# sbc.net
KiCad netlist of a schematic drawn in Altium Designer
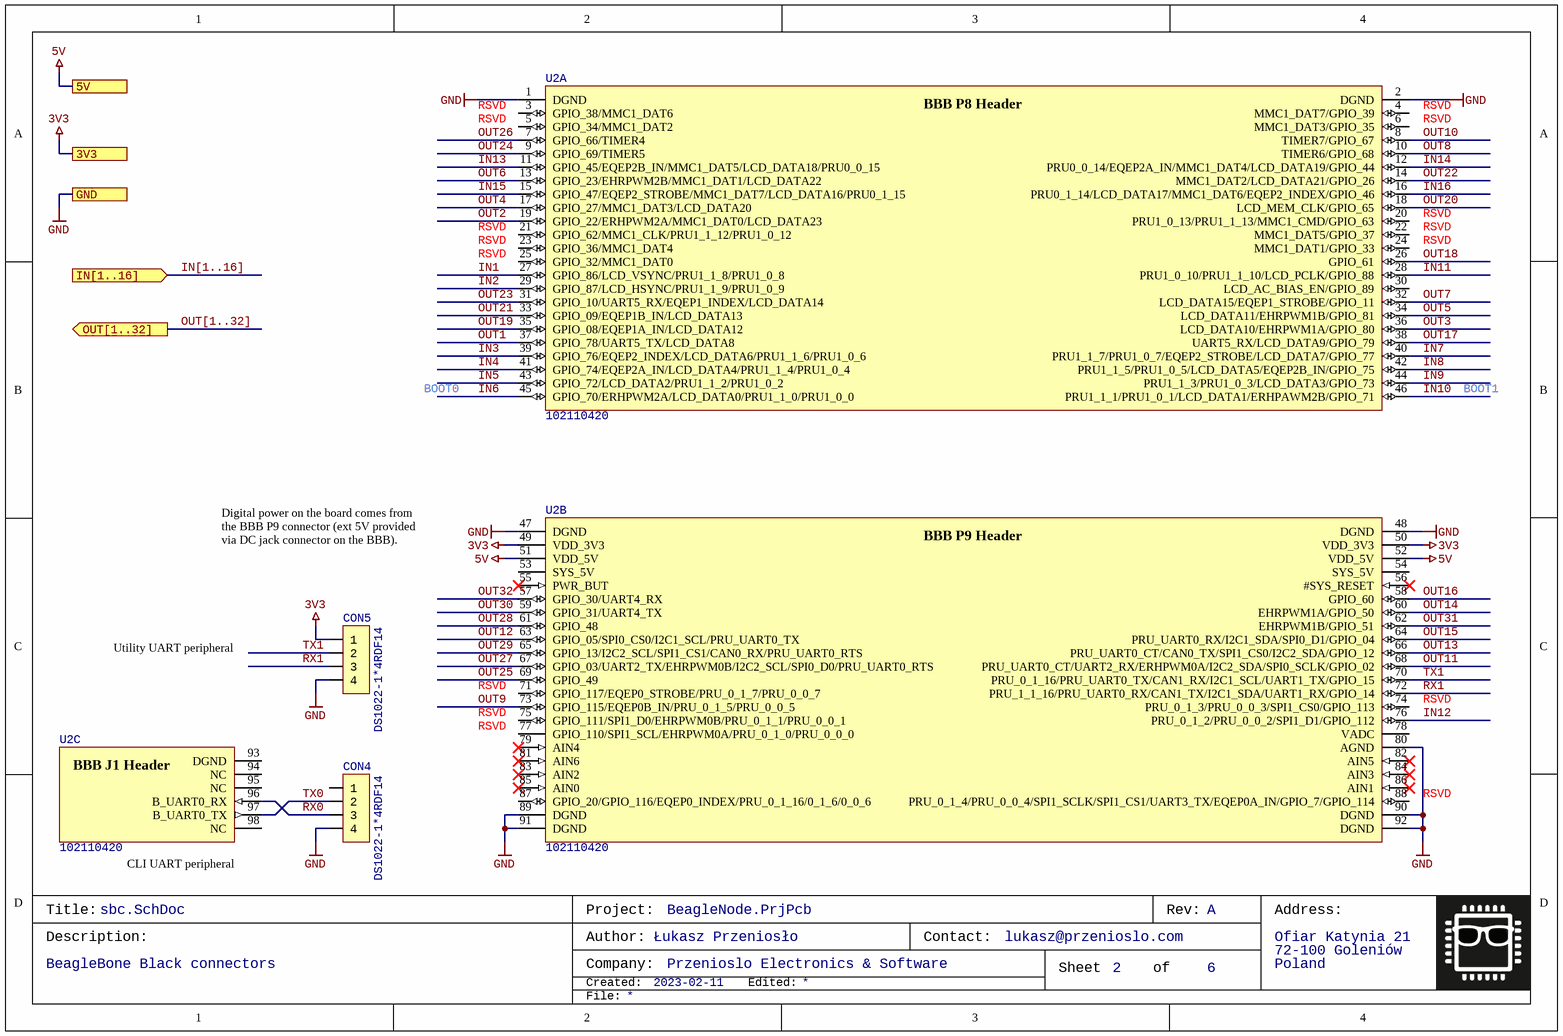
[diagram p0: sbc.SchDoc]

(export (version "E")
  (design (tool "Eeschema 10.0.6"))
  (components
    (comp (ref "CON4")
      (value "DS1022-1*4RDF14")
      (footprint "HMTA_1X4_2.54_3.60")
      (description "Pin header; pin strips; C-Grid III; male; PIN: 4; angled 90°; THT")
      (fields (field (name "MANUFACTURER") "CONNFLY"))
      (libsource (lib "connector") (part "HMTA_1X4_2.54_3.60"))
    )
    (comp (ref "CON5")
      (value "DS1022-1*4RDF14")
      (footprint "HMTA_1X4_2.54_3.60")
      (description "Pin header; pin strips; C-Grid III; male; PIN: 4; angled 90°; THT")
      (fields (field (name "MANUFACTURER") "CONNFLY"))
      (libsource (lib "connector") (part "HMTA_1X4_2.54_3.60"))
    )
    (comp (ref "U2")
      (value "102110420")
      (footprint "BeagleBone Black No Bat")
      (description "BeagleBone Black female headers without the battery 4 pin header")
      (fields (field (name "MANUFACTURER") "BeagleBoard"))
      (libsource (lib "shield") (part "Beaglebone Black No Bat"))
    )
  )
  (nets
    (net (code "1") (name "/IN1") (class "Default")
      (node (ref "U2") (pin "27") (pinfunction "GPIO_86/LCD_VSYNC/PRU1_1_8/PRU1_0_8_27") (pintype "bidirectional"))
    )
    (net (code "2") (name "/IN2") (class "Default")
      (node (ref "U2") (pin "29") (pinfunction "GPIO_87/LCD_HSYNC/PRU1_1_9/PRU1_0_9_29") (pintype "bidirectional"))
    )
    (net (code "3") (name "/IN3") (class "Default")
      (node (ref "U2") (pin "39") (pinfunction "GPIO_76/EQEP2_INDEX/LCD_DATA6/PRU1_1_6/PRU1_0_6_39") (pintype "bidirectional"))
    )
    (net (code "4") (name "/IN4") (class "Default")
      (node (ref "U2") (pin "41") (pinfunction "GPIO_74/EQEP2A_IN/LCD_DATA4/PRU1_1_4/PRU1_0_4_41") (pintype "bidirectional"))
    )
    (net (code "5") (name "/IN5") (class "Default")
      (node (ref "U2") (pin "43") (pinfunction "GPIO_72/LCD_DATA2/PRU1_1_2/PRU1_0_2_43") (pintype "bidirectional"))
    )
    (net (code "6") (name "/IN6") (class "Default")
      (node (ref "U2") (pin "45") (pinfunction "GPIO_70/ERHPWM2A/LCD_DATA0/PRU1_1_0/PRU1_0_0_45") (pintype "bidirectional"))
    )
    (net (code "7") (name "/IN7") (class "Default")
      (node (ref "U2") (pin "40") (pinfunction "PRU1_1_7/PRU1_0_7/EQEP2_STROBE/LCD_DATA7/GPIO_77_40") (pintype "bidirectional"))
    )
    (net (code "8") (name "/IN8") (class "Default")
      (node (ref "U2") (pin "42") (pinfunction "PRU1_1_5/PRU1_0_5/LCD_DATA5/EQEP2B_IN/GPIO_75_42") (pintype "bidirectional"))
    )
    (net (code "9") (name "/IN9") (class "Default")
      (node (ref "U2") (pin "44") (pinfunction "PRU1_1_3/PRU1_0_3/LCD_DATA3/GPIO_73_44") (pintype "bidirectional"))
    )
    (net (code "10") (name "/IN10") (class "Default")
      (node (ref "U2") (pin "46") (pinfunction "PRU1_1_1/PRU1_0_1/LCD_DATA1/ERHPAWM2B/GPIO_71_46") (pintype "bidirectional"))
    )
    (net (code "11") (name "/IN11") (class "Default")
      (node (ref "U2") (pin "28") (pinfunction "PRU1_0_10/PRU1_1_10/LCD_PCLK/GPIO_88_28") (pintype "bidirectional"))
    )
    (net (code "12") (name "/IN12") (class "Default")
      (node (ref "U2") (pin "76") (pinfunction "PRU_0_1_2/PRU_0_0_2/SPI1_D1/GPIO_112_76") (pintype "bidirectional"))
    )
    (net (code "13") (name "/IN13") (class "Default")
      (node (ref "U2") (pin "11") (pinfunction "GPIO_45/EQEP2B_IN/MMC1_DAT5/LCD_DATA18/PRU0_0_15_11") (pintype "bidirectional"))
    )
    (net (code "14") (name "/IN14") (class "Default")
      (node (ref "U2") (pin "12") (pinfunction "PRU0_0_14/EQEP2A_IN/MMC1_DAT4/LCD_DATA19/GPIO_44_12") (pintype "bidirectional"))
    )
    (net (code "15") (name "/IN15") (class "Default")
      (node (ref "U2") (pin "15") (pinfunction "GPIO_47/EQEP2_STROBE/MMC1_DAT7/LCD_DATA16/PRU0_1_15_15") (pintype "bidirectional"))
    )
    (net (code "16") (name "/IN16") (class "Default")
      (node (ref "U2") (pin "16") (pinfunction "PRU0_1_14/LCD_DATA17/MMC1_DAT6/EQEP2_INDEX/GPIO_46_16") (pintype "bidirectional"))
    )
    (net (code "18") (name "/OUT1") (class "Default")
      (node (ref "U2") (pin "37") (pinfunction "GPIO_78/UART5_TX/LCD_DATA8_37") (pintype "bidirectional"))
    )
    (net (code "19") (name "/OUT2") (class "Default")
      (node (ref "U2") (pin "19") (pinfunction "GPIO_22/ERHPWM2A/MMC1_DAT0/LCD_DATA23_19") (pintype "bidirectional"))
    )
    (net (code "20") (name "/OUT3") (class "Default")
      (node (ref "U2") (pin "36") (pinfunction "LCD_DATA10/EHRPWM1A/GPIO_80_36") (pintype "bidirectional"))
    )
    (net (code "21") (name "/OUT4") (class "Default")
      (node (ref "U2") (pin "17") (pinfunction "GPIO_27/MMC1_DAT3/LCD_DATA20_17") (pintype "bidirectional"))
    )
    (net (code "22") (name "/OUT5") (class "Default")
      (node (ref "U2") (pin "34") (pinfunction "LCD_DATA11/EHRPWM1B/GPIO_81_34") (pintype "bidirectional"))
    )
    (net (code "23") (name "/OUT6") (class "Default")
      (node (ref "U2") (pin "13") (pinfunction "GPIO_23/EHRPWM2B/MMC1_DAT1/LCD_DATA22_13") (pintype "bidirectional"))
    )
    (net (code "24") (name "/OUT7") (class "Default")
      (node (ref "U2") (pin "32") (pinfunction "LCD_DATA15/EQEP1_STROBE/GPIO_11_32") (pintype "bidirectional"))
    )
    (net (code "25") (name "/OUT8") (class "Default")
      (node (ref "U2") (pin "10") (pinfunction "TIMER6/GPIO_68_10") (pintype "bidirectional"))
    )
    (net (code "26") (name "/OUT9") (class "Default")
      (node (ref "U2") (pin "73") (pinfunction "GPIO_115/EQEP0B_IN/PRU_0_1_5/PRU_0_0_5_73") (pintype "bidirectional"))
    )
    (net (code "27") (name "/OUT10") (class "Default")
      (node (ref "U2") (pin "8") (pinfunction "TIMER7/GPIO_67_8") (pintype "bidirectional"))
    )
    (net (code "28") (name "/OUT11") (class "Default")
      (node (ref "U2") (pin "68") (pinfunction "PRU_UART0_CT/UART2_RX/ERHPWM0A/I2C2_SDA/SPI0_SCLK/GPIO_02_68") (pintype "bidirectional"))
    )
    (net (code "29") (name "/OUT12") (class "Default")
      (node (ref "U2") (pin "63") (pinfunction "GPIO_05/SPI0_CS0/I2C1_SCL/PRU_UART0_TX_63") (pintype "bidirectional"))
    )
    (net (code "30") (name "/OUT13") (class "Default")
      (node (ref "U2") (pin "66") (pinfunction "PRU_UART0_CT/CAN0_TX/SPI1_CS0/I2C2_SDA/GPIO_12_66") (pintype "bidirectional"))
    )
    (net (code "31") (name "/OUT14") (class "Default")
      (node (ref "U2") (pin "60") (pinfunction "EHRPWM1A/GPIO_50_60") (pintype "bidirectional"))
    )
    (net (code "32") (name "/OUT15") (class "Default")
      (node (ref "U2") (pin "64") (pinfunction "PRU_UART0_RX/I2C1_SDA/SPI0_D1/GPIO_04_64") (pintype "bidirectional"))
    )
    (net (code "33") (name "/OUT16") (class "Default")
      (node (ref "U2") (pin "58") (pinfunction "GPIO_60_58") (pintype "bidirectional"))
    )
    (net (code "34") (name "/OUT17") (class "Default")
      (node (ref "U2") (pin "38") (pinfunction "UART5_RX/LCD_DATA9/GPIO_79_38") (pintype "bidirectional"))
    )
    (net (code "35") (name "/OUT18") (class "Default")
      (node (ref "U2") (pin "26") (pinfunction "GPIO_61_26") (pintype "bidirectional"))
    )
    (net (code "36") (name "/OUT19") (class "Default")
      (node (ref "U2") (pin "35") (pinfunction "GPIO_08/EQEP1A_IN/LCD_DATA12_35") (pintype "bidirectional"))
    )
    (net (code "37") (name "/OUT20") (class "Default")
      (node (ref "U2") (pin "18") (pinfunction "LCD_MEM_CLK/GPIO_65_18") (pintype "bidirectional"))
    )
    (net (code "38") (name "/OUT21") (class "Default")
      (node (ref "U2") (pin "33") (pinfunction "GPIO_09/EQEP1B_IN/LCD_DATA13_33") (pintype "bidirectional"))
    )
    (net (code "39") (name "/OUT22") (class "Default")
      (node (ref "U2") (pin "14") (pinfunction "MMC1_DAT2/LCD_DATA21/GPIO_26_14") (pintype "bidirectional"))
    )
    (net (code "40") (name "/OUT23") (class "Default")
      (node (ref "U2") (pin "31") (pinfunction "GPIO_10/UART5_RX/EQEP1_INDEX/LCD_DATA14_31") (pintype "bidirectional"))
    )
    (net (code "41") (name "/OUT24") (class "Default")
      (node (ref "U2") (pin "9") (pinfunction "GPIO_69/TIMER5_9") (pintype "bidirectional"))
    )
    (net (code "42") (name "/OUT25") (class "Default")
      (node (ref "U2") (pin "69") (pinfunction "GPIO_49_69") (pintype "bidirectional"))
    )
    (net (code "43") (name "/OUT26") (class "Default")
      (node (ref "U2") (pin "7") (pinfunction "GPIO_66/TIMER4_7") (pintype "bidirectional"))
    )
    (net (code "44") (name "/OUT27") (class "Default")
      (node (ref "U2") (pin "67") (pinfunction "GPIO_03/UART2_TX/EHRPWM0B/I2C2_SCL/SPI0_D0/PRU_UART0_RTS_67") (pintype "bidirectional"))
    )
    (net (code "45") (name "/OUT28") (class "Default")
      (node (ref "U2") (pin "61") (pinfunction "GPIO_48_61") (pintype "bidirectional"))
    )
    (net (code "46") (name "/OUT29") (class "Default")
      (node (ref "U2") (pin "65") (pinfunction "GPIO_13/I2C2_SCL/SPI1_CS1/CAN0_RX/PRU_UART0_RTS_65") (pintype "bidirectional"))
    )
    (net (code "47") (name "/OUT30") (class "Default")
      (node (ref "U2") (pin "59") (pinfunction "GPIO_31/UART4_TX_59") (pintype "bidirectional"))
    )
    (net (code "48") (name "/OUT31") (class "Default")
      (node (ref "U2") (pin "62") (pinfunction "EHRPWM1B/GPIO_51_62") (pintype "bidirectional"))
    )
    (net (code "49") (name "/OUT32") (class "Default")
      (node (ref "U2") (pin "57") (pinfunction "GPIO_30/UART4_RX_57") (pintype "bidirectional"))
    )
    (net (code "51") (name "/RX0") (class "Default")
      (node (ref "CON4") (pin "3") (pinfunction "3_3") (pintype "passive"))
      (node (ref "U2") (pin "96") (pinfunction "B_UART0_RX_96") (pintype "input"))
    )
    (net (code "52") (name "/RX1") (class "Default")
      (node (ref "CON5") (pin "3") (pinfunction "3_3") (pintype "passive"))
      (node (ref "U2") (pin "72") (pinfunction "PRU_1_1_16/PRU_UART0_RX/CAN1_TX/I2C1_SDA/UART1_RX/GPIO_14_72") (pintype "bidirectional"))
    )
    (net (code "53") (name "/TX0") (class "Default")
      (node (ref "CON4") (pin "2") (pinfunction "2_2") (pintype "passive"))
      (node (ref "U2") (pin "97") (pinfunction "B_UART0_TX_97") (pintype "output"))
    )
    (net (code "54") (name "/TX1") (class "Default")
      (node (ref "CON5") (pin "2") (pinfunction "2_2") (pintype "passive"))
      (node (ref "U2") (pin "70") (pinfunction "PRU_0_1_16/PRU_UART0_TX/CAN1_RX/I2C1_SCL/UART1_TX/GPIO_15_70") (pintype "bidirectional"))
    )
    (net (code "55") (name "3V3") (class "Default")
      (node (ref "CON5") (pin "1") (pinfunction "1_1") (pintype "passive"))
      (node (ref "U2") (pin "49") (pinfunction "VDD_3V3_49") (pintype "power_in"))
      (node (ref "U2") (pin "50") (pinfunction "VDD_3V3_50") (pintype "power_in"))
    )
    (net (code "56") (name "5V") (class "Default")
      (node (ref "U2") (pin "51") (pinfunction "VDD_5V_51") (pintype "power_in"))
      (node (ref "U2") (pin "52") (pinfunction "VDD_5V_52") (pintype "power_in"))
    )
    (net (code "57") (name "GND") (class "Default")
      (node (ref "CON4") (pin "4") (pinfunction "4_4") (pintype "passive"))
      (node (ref "CON5") (pin "4") (pinfunction "4_4") (pintype "passive"))
      (node (ref "U2") (pin "1") (pinfunction "DGND_1") (pintype "power_in"))
      (node (ref "U2") (pin "2") (pinfunction "DGND_2") (pintype "power_in"))
      (node (ref "U2") (pin "47") (pinfunction "DGND_47") (pintype "power_in"))
      (node (ref "U2") (pin "48") (pinfunction "DGND_48") (pintype "power_in"))
      (node (ref "U2") (pin "80") (pinfunction "AGND_80") (pintype "power_in"))
      (node (ref "U2") (pin "89") (pinfunction "DGND_89") (pintype "power_in"))
      (node (ref "U2") (pin "90") (pinfunction "DGND_90") (pintype "power_in"))
      (node (ref "U2") (pin "91") (pinfunction "DGND_91") (pintype "power_in"))
      (node (ref "U2") (pin "92") (pinfunction "DGND_92") (pintype "power_in"))
    )
    (net (code "58") (name "unconnected-(CON4-Pad1)") (class "Default")
      (node (ref "CON4") (pin "1") (pinfunction "1_1") (pintype "passive"))
    )
    (net (code "59") (name "unconnected-(U2A-GPIO_32{slash}MMC1_DAT0-Pad25)") (class "Default")
      (node (ref "U2") (pin "25") (pinfunction "GPIO_32/MMC1_DAT0_25") (pintype "bidirectional"))
    )
    (net (code "60") (name "unconnected-(U2A-GPIO_34{slash}MMC1_DAT2-Pad5)") (class "Default")
      (node (ref "U2") (pin "5") (pinfunction "GPIO_34/MMC1_DAT2_5") (pintype "bidirectional"))
    )
    (net (code "61") (name "unconnected-(U2A-GPIO_36{slash}MMC1_DAT4-Pad23)") (class "Default")
      (node (ref "U2") (pin "23") (pinfunction "GPIO_36/MMC1_DAT4_23") (pintype "bidirectional"))
    )
    (net (code "62") (name "unconnected-(U2A-GPIO_38{slash}MMC1_DAT6-Pad3)") (class "Default")
      (node (ref "U2") (pin "3") (pinfunction "GPIO_38/MMC1_DAT6_3") (pintype "bidirectional"))
    )
    (net (code "63") (name "unconnected-(U2A-GPIO_62{slash}MMC1_CLK{slash}PRU1_1_12{slash}PRU1_0_12-Pad21)") (class "Default")
      (node (ref "U2") (pin "21") (pinfunction "GPIO_62/MMC1_CLK/PRU1_1_12/PRU1_0_12_21") (pintype "bidirectional"))
    )
    (net (code "64") (name "unconnected-(U2A-LCD_AC_BIAS_EN{slash}GPIO_89-Pad30)") (class "Default")
      (node (ref "U2") (pin "30") (pinfunction "LCD_AC_BIAS_EN/GPIO_89_30") (pintype "bidirectional"))
    )
    (net (code "65") (name "unconnected-(U2A-MMC1_DAT1{slash}GPIO_33-Pad24)") (class "Default")
      (node (ref "U2") (pin "24") (pinfunction "MMC1_DAT1/GPIO_33_24") (pintype "bidirectional"))
    )
    (net (code "66") (name "unconnected-(U2A-MMC1_DAT3{slash}GPIO_35-Pad6)") (class "Default")
      (node (ref "U2") (pin "6") (pinfunction "MMC1_DAT3/GPIO_35_6") (pintype "bidirectional"))
    )
    (net (code "67") (name "unconnected-(U2A-MMC1_DAT5{slash}GPIO_37-Pad22)") (class "Default")
      (node (ref "U2") (pin "22") (pinfunction "MMC1_DAT5/GPIO_37_22") (pintype "bidirectional"))
    )
    (net (code "68") (name "unconnected-(U2A-MMC1_DAT7{slash}GPIO_39-Pad4)") (class "Default")
      (node (ref "U2") (pin "4") (pinfunction "MMC1_DAT7/GPIO_39_4") (pintype "bidirectional"))
    )
    (net (code "69") (name "unconnected-(U2A-PRU1_0_13{slash}PRU1_1_13{slash}MMC1_CMD{slash}GPIO_63-Pad20)") (class "Default")
      (node (ref "U2") (pin "20") (pinfunction "PRU1_0_13/PRU1_1_13/MMC1_CMD/GPIO_63_20") (pintype "bidirectional"))
    )
    (net (code "70") (name "unconnected-(U2B-#SYS_RESET-Pad56)") (class "Default")
      (node (ref "U2") (pin "56") (pinfunction "#SYS_RESET_56") (pintype "input+no_connect"))
    )
    (net (code "71") (name "unconnected-(U2B-AIN0-Pad85)") (class "Default")
      (node (ref "U2") (pin "85") (pinfunction "AIN0_85") (pintype "input+no_connect"))
    )
    (net (code "72") (name "unconnected-(U2B-AIN1-Pad86)") (class "Default")
      (node (ref "U2") (pin "86") (pinfunction "AIN1_86") (pintype "input+no_connect"))
    )
    (net (code "73") (name "unconnected-(U2B-AIN2-Pad83)") (class "Default")
      (node (ref "U2") (pin "83") (pinfunction "AIN2_83") (pintype "input+no_connect"))
    )
    (net (code "74") (name "unconnected-(U2B-AIN3-Pad84)") (class "Default")
      (node (ref "U2") (pin "84") (pinfunction "AIN3_84") (pintype "input+no_connect"))
    )
    (net (code "75") (name "unconnected-(U2B-AIN4-Pad79)") (class "Default")
      (node (ref "U2") (pin "79") (pinfunction "AIN4_79") (pintype "input+no_connect"))
    )
    (net (code "76") (name "unconnected-(U2B-AIN5-Pad82)") (class "Default")
      (node (ref "U2") (pin "82") (pinfunction "AIN5_82") (pintype "input+no_connect"))
    )
    (net (code "77") (name "unconnected-(U2B-AIN6-Pad81)") (class "Default")
      (node (ref "U2") (pin "81") (pinfunction "AIN6_81") (pintype "input+no_connect"))
    )
    (net (code "78") (name "unconnected-(U2B-GPIO_20{slash}GPIO_116{slash}EQEP0_INDEX{slash}PRU_0_1_16{slash}0_1_6{slash}0_0_6-Pad87)") (class "Default")
      (node (ref "U2") (pin "87") (pinfunction "GPIO_20/GPIO_116/EQEP0_INDEX/PRU_0_1_16/0_1_6/0_0_6_87") (pintype "bidirectional"))
    )
    (net (code "79") (name "unconnected-(U2B-GPIO_110{slash}SPI1_SCL{slash}EHRPWM0A{slash}PRU_0_1_0{slash}PRU_0_0_0-Pad77)") (class "Default")
      (node (ref "U2") (pin "77") (pinfunction "GPIO_110/SPI1_SCL/EHRPWM0A/PRU_0_1_0/PRU_0_0_0_77") (pintype "passive"))
    )
    (net (code "80") (name "unconnected-(U2B-GPIO_111{slash}SPI1_D0{slash}EHRPWM0B{slash}PRU_0_1_1{slash}PRU_0_0_1-Pad75)") (class "Default")
      (node (ref "U2") (pin "75") (pinfunction "GPIO_111/SPI1_D0/EHRPWM0B/PRU_0_1_1/PRU_0_0_1_75") (pintype "bidirectional"))
    )
    (net (code "81") (name "unconnected-(U2B-GPIO_117{slash}EQEP0_STROBE{slash}PRU_0_1_7{slash}PRU_0_0_7-Pad71)") (class "Default")
      (node (ref "U2") (pin "71") (pinfunction "GPIO_117/EQEP0_STROBE/PRU_0_1_7/PRU_0_0_7_71") (pintype "bidirectional"))
    )
    (net (code "82") (name "unconnected-(U2B-PRU_0_1_3{slash}PRU_0_0_3{slash}SPI1_CS0{slash}GPIO_113-Pad74)") (class "Default")
      (node (ref "U2") (pin "74") (pinfunction "PRU_0_1_3/PRU_0_0_3/SPI1_CS0/GPIO_113_74") (pintype "bidirectional"))
    )
    (net (code "83") (name "unconnected-(U2B-PRU_0_1_4{slash}PRU_0_0_4{slash}SPI1_SCLK{slash}SPI1_CS1{slash}UART3_TX{slash}EQEP0A_IN{slash}GPIO_7{slash}GPIO_114-Pad88)") (class "Default")
      (node (ref "U2") (pin "88") (pinfunction "PRU_0_1_4/PRU_0_0_4/SPI1_SCLK/SPI1_CS1/UART3_TX/EQEP0A_IN/GPIO_7/GPIO_114_88") (pintype "bidirectional"))
    )
    (net (code "84") (name "unconnected-(U2B-PWR_BUT-Pad55)") (class "Default")
      (node (ref "U2") (pin "55") (pinfunction "PWR_BUT_55") (pintype "input+no_connect"))
    )
    (net (code "85") (name "unconnected-(U2B-SYS_5V-Pad53)") (class "Default")
      (node (ref "U2") (pin "53") (pinfunction "SYS_5V_53") (pintype "power_in"))
    )
    (net (code "86") (name "unconnected-(U2B-SYS_5V-Pad54)") (class "Default")
      (node (ref "U2") (pin "54") (pinfunction "SYS_5V_54") (pintype "power_in"))
    )
    (net (code "87") (name "unconnected-(U2B-VADC-Pad78)") (class "Default")
      (node (ref "U2") (pin "78") (pinfunction "VADC_78") (pintype "power_in"))
    )
    (net (code "88") (name "unconnected-(U2C-DGND-Pad93)") (class "Default")
      (node (ref "U2") (pin "93") (pinfunction "DGND_93") (pintype "power_in"))
    )
    (net (code "89") (name "unconnected-(U2C-NC-Pad94)") (class "Default")
      (node (ref "U2") (pin "94") (pinfunction "NC_94") (pintype "passive"))
    )
    (net (code "90") (name "unconnected-(U2C-NC-Pad95)") (class "Default")
      (node (ref "U2") (pin "95") (pinfunction "NC_95") (pintype "passive"))
    )
    (net (code "91") (name "unconnected-(U2C-NC-Pad98)") (class "Default")
      (node (ref "U2") (pin "98") (pinfunction "NC_98") (pintype "passive"))
    )
  )
)
